# PSU.net
KiCad netlist of a schematic drawn in Altium Designer
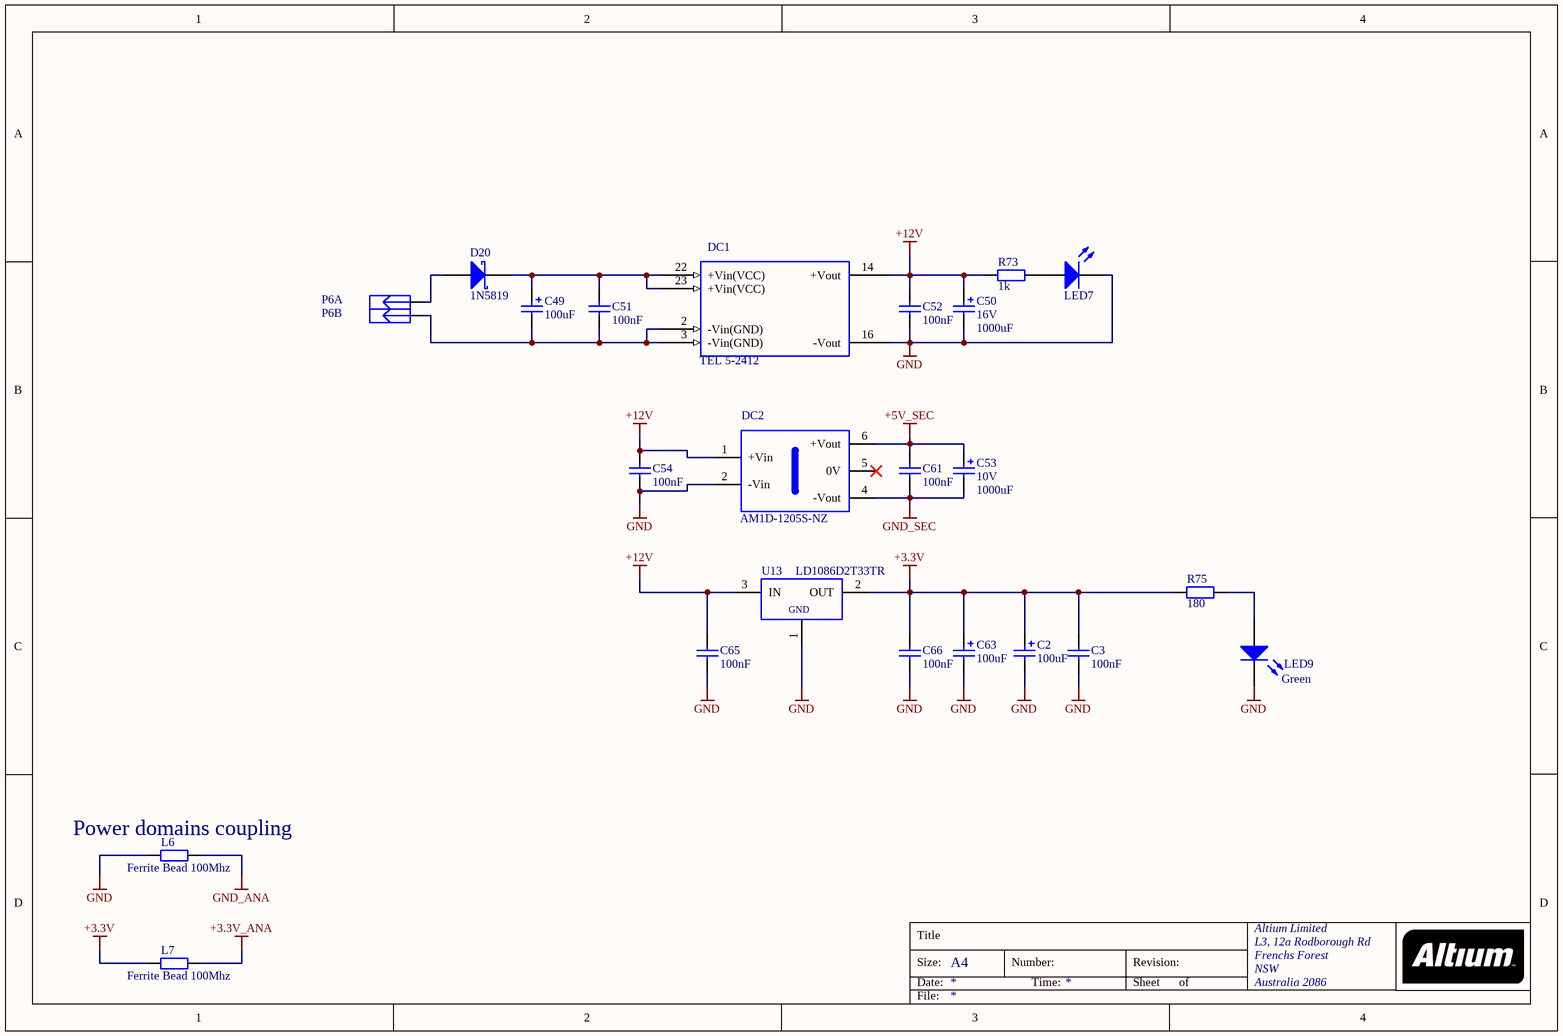
[diagram p0: PSU.SchDoc]

(export (version "E")
  (design (tool "Eeschema 10.0.6"))
  (components
    (comp (ref "C2")
      (value "100uF")
      (footprint "CAPPR3.5-8x12")
      (fields (field (name "Comment") "Cap"))
      (libsource (lib "Capacitors") (part "Cap pol"))
    )
    (comp (ref "C3")
      (value "100nF")
      (footprint "1206_REFLOW")
      (fields (field (name "Comment") "Cap 1206"))
      (libsource (lib "Capacitors") (part "Cap 1206"))
    )
    (comp (ref "C49")
      (value "100uF")
      (footprint "CAPPR3.5-8x12")
      (fields (field (name "Comment") "Cap"))
      (libsource (lib "Capacitors") (part "Cap pol"))
    )
    (comp (ref "C50")
      (value "1000uF")
      (footprint "RA_8.0_RM3.5")
      (fields (field (name "VOLTAGE") "16V") (field (name "Comment") "Cap"))
      (libsource (lib "Capacitors") (part "Cap pol"))
    )
    (comp (ref "C51")
      (value "100nF")
      (footprint "1206_REFLOW")
      (fields (field (name "Comment") "Cap 1206"))
      (libsource (lib "Capacitors") (part "Cap 1206"))
    )
    (comp (ref "C52")
      (value "100nF")
      (footprint "1206_REFLOW")
      (fields (field (name "Comment") "Cap 1206"))
      (libsource (lib "Capacitors") (part "Cap 1206"))
    )
    (comp (ref "C53")
      (value "1000uF")
      (footprint "RA_8.0_RM3.5")
      (fields (field (name "VOLTAGE") "10V") (field (name "Comment") "Cap"))
      (libsource (lib "Capacitors") (part "Cap pol"))
    )
    (comp (ref "C54")
      (value "100nF")
      (footprint "1206_REFLOW")
      (fields (field (name "Comment") "Cap 1206"))
      (libsource (lib "Capacitors") (part "Cap 1206"))
    )
    (comp (ref "C61")
      (value "100nF")
      (footprint "1206_REFLOW")
      (fields (field (name "Comment") "Cap 1206"))
      (libsource (lib "Capacitors") (part "Cap 1206"))
    )
    (comp (ref "C63")
      (value "100uF")
      (footprint "CAPPR3.5-8x12")
      (fields (field (name "Comment") "Cap"))
      (libsource (lib "Capacitors") (part "Cap pol"))
    )
    (comp (ref "C65")
      (value "100nF")
      (footprint "1206_REFLOW")
      (fields (field (name "Comment") "Cap 1206"))
      (libsource (lib "Capacitors") (part "Cap 1206"))
    )
    (comp (ref "C66")
      (value "100nF")
      (footprint "1206_REFLOW")
      (fields (field (name "Comment") "Cap 1206"))
      (libsource (lib "Capacitors") (part "Cap 1206"))
    )
    (comp (ref "D20")
      (value "1N5819")
      (footprint "DO-214_S1A(Primary)")
      (libsource (lib "Diode") (part "1N5819"))
    )
    (comp (ref "DC1")
      (value "TEL 5-2412")
      (footprint "DIP24_TRACO")
      (description "DC/DC CONVERTER, 3W 5V")
      (fields (field (name "MANUFACTURER") "CINCON") (field (name "MFRR. PART NO.") "EC3A21HM"))
      (libsource (lib "DC-DC") (part "EC3A21HM"))
    )
    (comp (ref "DC2")
      (value "AM1D-1205S-NZ")
      (footprint "-AM1D_AM1D-D(Primary)")
      (description "AM1D-D")
      (libsource (lib "DC-DC") (part "AM1D-D"))
    )
    (comp (ref "L6")
      (value "Ferrite Bead 100Mhz")
      (footprint "1206_REFLOW")
      (fields (field (name "Comment") "RES"))
      (libsource (lib "Resistor") (part "RES 1"))
    )
    (comp (ref "L7")
      (value "Ferrite Bead 100Mhz")
      (footprint "1206_REFLOW")
      (fields (field (name "Comment") "RES"))
      (libsource (lib "Resistor") (part "RES 1"))
    )
    (comp (ref "LED7") (value "LED") (footprint "LED_1206") (libsource (lib "LED") (part "LED")))
    (comp (ref "LED9") (value "Green") (footprint "LED_1206") (libsource (lib "LED") (part "LED")))
    (comp (ref "P6")
      (value "MSTBA 2,5/ 2-G-5,08")
      (footprint "STLZ950 2G-5.08-H")
      (description "Header, right angled, 12 A, 250 V, pitch 5.08 mm, No. of poles:2")
      (fields (field (name "MANUFACTURER") "Phoenix") (field (name "MFRR. PART NO.") "1757242"))
      (libsource (lib "Connector IDS") (part "MSTBA 2,5/ 2-G-5,08"))
    )
    (comp (ref "R73")
      (value "1k")
      (footprint "1206_REFLOW")
      (fields (field (name "Comment") "RES"))
      (libsource (lib "Resistor") (part "RES 1"))
    )
    (comp (ref "R75")
      (value "180")
      (footprint "1206_REFLOW")
      (fields (field (name "Comment") "RES"))
      (libsource (lib "Resistor") (part "RES 1"))
    )
    (comp (ref "U13")
      (value "LD1086D2T33TR")
      (footprint "D2PAK")
      (description "STMICROELECTRONICS - LD1086D2T33TR - IC, V REG, LDO 3.3V, SMD")
      (libsource (lib "Voltage_Regulator") (part "LD1086-XX"))
    )
  )
  (nets
    (net (code "1") (name "+3.3V") (class "Default")
      (node (ref "C2") (pin "1") (pinfunction "1_1") (pintype "passive"))
      (node (ref "C3") (pin "2") (pinfunction "2_2") (pintype "passive"))
      (node (ref "C63") (pin "1") (pinfunction "1_1") (pintype "passive"))
      (node (ref "C66") (pin "2") (pinfunction "2_2") (pintype "passive"))
      (node (ref "L7") (pin "1") (pinfunction "1_1") (pintype "passive"))
      (node (ref "R75") (pin "1") (pinfunction "1_1") (pintype "passive"))
      (node (ref "U13") (pin "2") (pinfunction "OUT_2") (pintype "power_in"))
    )
    (net (code "2") (name "+3.3V_ANA") (class "Default")
      (node (ref "L7") (pin "2") (pinfunction "2_2") (pintype "passive"))
    )
    (net (code "3") (name "+5V_SEC") (class "Default")
      (node (ref "C53") (pin "1") (pinfunction "1_1") (pintype "passive"))
      (node (ref "C61") (pin "2") (pinfunction "2_2") (pintype "passive"))
      (node (ref "DC2") (pin "6") (pinfunction "+Vout_6") (pintype "power_in"))
    )
    (net (code "4") (name "+12V") (class "Default")
      (node (ref "C50") (pin "1") (pinfunction "1_1") (pintype "passive"))
      (node (ref "C52") (pin "2") (pinfunction "2_2") (pintype "passive"))
      (node (ref "C54") (pin "2") (pinfunction "2_2") (pintype "passive"))
      (node (ref "C65") (pin "2") (pinfunction "2_2") (pintype "passive"))
      (node (ref "DC1") (pin "14") (pinfunction "+Vout_14") (pintype "power_in"))
      (node (ref "DC2") (pin "1") (pinfunction "+Vin_1") (pintype "power_in"))
      (node (ref "R73") (pin "1") (pinfunction "1_1") (pintype "passive"))
      (node (ref "U13") (pin "3") (pinfunction "IN_3") (pintype "power_in"))
    )
    (net (code "5") (name "GND") (class "Default")
      (node (ref "C2") (pin "2") (pinfunction "2_2") (pintype "passive"))
      (node (ref "C3") (pin "1") (pinfunction "1_1") (pintype "passive"))
      (node (ref "C50") (pin "2") (pinfunction "2_2") (pintype "passive"))
      (node (ref "C52") (pin "1") (pinfunction "1_1") (pintype "passive"))
      (node (ref "C54") (pin "1") (pinfunction "1_1") (pintype "passive"))
      (node (ref "C63") (pin "2") (pinfunction "2_2") (pintype "passive"))
      (node (ref "C65") (pin "1") (pinfunction "1_1") (pintype "passive"))
      (node (ref "C66") (pin "1") (pinfunction "1_1") (pintype "passive"))
      (node (ref "DC1") (pin "16") (pinfunction "-Vout_16") (pintype "power_in"))
      (node (ref "DC2") (pin "2") (pinfunction "-Vin_2") (pintype "power_in"))
      (node (ref "L6") (pin "1") (pinfunction "1_1") (pintype "passive"))
      (node (ref "LED7") (pin "K") (pinfunction "K_K") (pintype "passive"))
      (node (ref "LED9") (pin "K") (pinfunction "K_K") (pintype "passive"))
      (node (ref "U13") (pin "1") (pinfunction "GND_1") (pintype "power_in"))
    )
    (net (code "6") (name "GND_ANA") (class "Default")
      (node (ref "L6") (pin "2") (pinfunction "2_2") (pintype "passive"))
    )
    (net (code "7") (name "GND_SEC") (class "Default")
      (node (ref "C53") (pin "2") (pinfunction "2_2") (pintype "passive"))
      (node (ref "C61") (pin "1") (pinfunction "1_1") (pintype "passive"))
      (node (ref "DC2") (pin "4") (pinfunction "-Vout_4") (pintype "power_in"))
    )
    (net (code "8") (name "Net-(C49-Pad1)") (class "Default")
      (node (ref "C49") (pin "1") (pinfunction "1_1") (pintype "passive"))
      (node (ref "C51") (pin "2") (pinfunction "2_2") (pintype "passive"))
      (node (ref "D20") (pin "K") (pinfunction "K_K") (pintype "passive"))
      (node (ref "DC1") (pin "22") (pinfunction "+Vin(VCC)_22") (pintype "input"))
      (node (ref "DC1") (pin "23") (pinfunction "+Vin(VCC)_23") (pintype "input"))
    )
    (net (code "9") (name "Net-(LED7-PadA)") (class "Default")
      (node (ref "LED7") (pin "A") (pinfunction "A_A") (pintype "passive"))
      (node (ref "R73") (pin "2") (pinfunction "2_2") (pintype "passive"))
    )
    (net (code "10") (name "Net-(LED9-PadA)") (class "Default")
      (node (ref "LED9") (pin "A") (pinfunction "A_A") (pintype "passive"))
      (node (ref "R75") (pin "2") (pinfunction "2_2") (pintype "passive"))
    )
    (net (code "11") (name "Net-(P6A-SIG)") (class "Default")
      (node (ref "D20") (pin "A") (pinfunction "A_A") (pintype "passive"))
      (node (ref "P6") (pin "1") (pinfunction "SIG_1") (pintype "passive"))
    )
    (net (code "12") (name "Net-(P6B-SIG)") (class "Default")
      (node (ref "C49") (pin "2") (pinfunction "2_2") (pintype "passive"))
      (node (ref "C51") (pin "1") (pinfunction "1_1") (pintype "passive"))
      (node (ref "DC1") (pin "2") (pinfunction "-Vin(GND)_2") (pintype "input"))
      (node (ref "DC1") (pin "3") (pinfunction "-Vin(GND)_3") (pintype "input"))
      (node (ref "P6") (pin "2") (pinfunction "SIG_2") (pintype "passive"))
    )
    (net (code "13") (name "unconnected-(DC2-0V-Pad5)") (class "Default")
      (node (ref "DC2") (pin "5") (pinfunction "0V_5") (pintype "power_in+no_connect"))
    )
  )
)
